# memory-game.net
KiCad netlist of a schematic drawn in EasyEDA
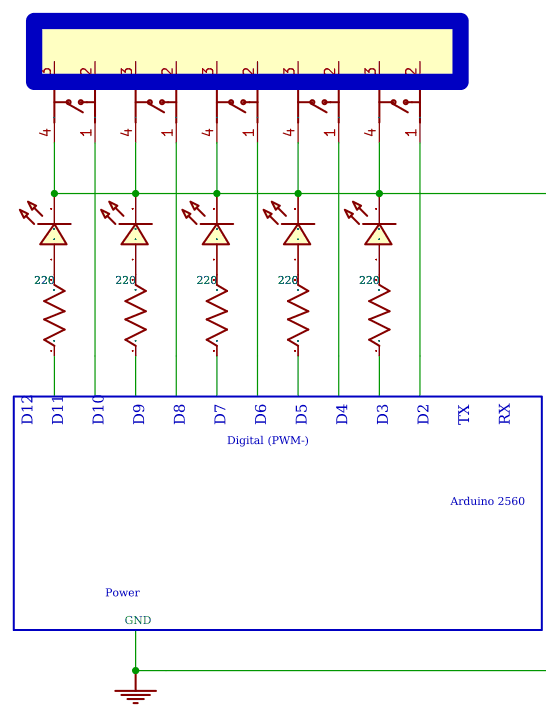
[diagram p0: schematic sheet]

(export (version "E")
  (design (tool "Eeschema 10.0.6"))
  (components
    (comp (ref "KEY1")
      (value "button6*6*8")
      (fields (field (name "BOM_Supplier Part") "C59982"))
      (libsource (lib "") (part "button6*6*8"))
    )
    (comp (ref "KEY2")
      (value "button6*6*8")
      (fields (field (name "BOM_Supplier Part") "C59982"))
      (libsource (lib "") (part "button6*6*8"))
    )
    (comp (ref "KEY3")
      (value "button6*6*8")
      (fields (field (name "BOM_Supplier Part") "C59982"))
      (libsource (lib "") (part "button6*6*8"))
    )
    (comp (ref "KEY4")
      (value "button6*6*8")
      (fields (field (name "BOM_Supplier Part") "C59982"))
      (libsource (lib "") (part "button6*6*8"))
    )
    (comp (ref "KEY5")
      (value "button6*6*8")
      (fields (field (name "BOM_Supplier Part") "C59982"))
      (libsource (lib "") (part "button6*6*8"))
    )
    (comp (ref "LED1")
      (value "LED-0603_R")
      (fields
        (field (name "BOM_Manufacturer Part") "19-217/R6C-AL1M2VY/3T")
        (field (name "BOM_Supplier Part") "C72044")
      )
      (libsource (lib "") (part "LED-0603_R"))
    )
    (comp (ref "LED2")
      (value "LED-0603_R")
      (fields
        (field (name "BOM_Manufacturer Part") "19-217/R6C-AL1M2VY/3T")
        (field (name "BOM_Supplier Part") "C72044")
      )
      (libsource (lib "") (part "LED-0603_R"))
    )
    (comp (ref "LED3")
      (value "LED-0603_R")
      (fields
        (field (name "BOM_Manufacturer Part") "19-217/R6C-AL1M2VY/3T")
        (field (name "BOM_Supplier Part") "C72044")
      )
      (libsource (lib "") (part "LED-0603_R"))
    )
    (comp (ref "LED4")
      (value "LED-0603_R")
      (fields
        (field (name "BOM_Manufacturer Part") "19-217/R6C-AL1M2VY/3T")
        (field (name "BOM_Supplier Part") "C72044")
      )
      (libsource (lib "") (part "LED-0603_R"))
    )
    (comp (ref "LED5")
      (value "LED-0603_R")
      (fields
        (field (name "BOM_Manufacturer Part") "19-217/R6C-AL1M2VY/3T")
        (field (name "BOM_Supplier Part") "C72044")
      )
      (libsource (lib "") (part "LED-0603_R"))
    )
    (comp (ref "R1") (value "220") (libsource (lib "") (part "R_0603_US")))
    (comp (ref "R2") (value "220") (libsource (lib "") (part "R_0603_US")))
    (comp (ref "R3") (value "220") (libsource (lib "") (part "R_0603_US")))
    (comp (ref "R4") (value "220") (libsource (lib "") (part "R_0603_US")))
    (comp (ref "R5") (value "220") (libsource (lib "") (part "R_0603_US")))
  )
  (nets
    (net (code "1") (name "GND") (class "Default")
      (node (ref "KEY1") (pin "4") (pinfunction "4_4") (pintype "unspecified"))
      (node (ref "KEY2") (pin "4") (pinfunction "4_4") (pintype "unspecified"))
      (node (ref "KEY3") (pin "4") (pinfunction "4_4") (pintype "unspecified"))
      (node (ref "KEY4") (pin "4") (pinfunction "4_4") (pintype "unspecified"))
      (node (ref "KEY5") (pin "4") (pinfunction "4_4") (pintype "unspecified"))
      (node (ref "LED1") (pin "2") (pinfunction "2_2") (pintype "unspecified"))
      (node (ref "LED2") (pin "2") (pinfunction "2_2") (pintype "unspecified"))
      (node (ref "LED3") (pin "2") (pinfunction "2_2") (pintype "unspecified"))
      (node (ref "LED4") (pin "2") (pinfunction "2_2") (pintype "unspecified"))
      (node (ref "LED5") (pin "2") (pinfunction "2_2") (pintype "unspecified"))
    )
    (net (code "2") (name "Net-(LED1-Pad1)") (class "Default")
      (node (ref "LED1") (pin "1") (pinfunction "1_1") (pintype "unspecified"))
      (node (ref "R1") (pin "2") (pinfunction "2_2") (pintype "unspecified"))
    )
    (net (code "3") (name "Net-(LED2-Pad1)") (class "Default")
      (node (ref "LED2") (pin "1") (pinfunction "1_1") (pintype "unspecified"))
      (node (ref "R5") (pin "2") (pinfunction "2_2") (pintype "unspecified"))
    )
    (net (code "4") (name "Net-(LED3-Pad1)") (class "Default")
      (node (ref "LED3") (pin "1") (pinfunction "1_1") (pintype "unspecified"))
      (node (ref "R4") (pin "2") (pinfunction "2_2") (pintype "unspecified"))
    )
    (net (code "5") (name "Net-(LED4-Pad1)") (class "Default")
      (node (ref "LED4") (pin "1") (pinfunction "1_1") (pintype "unspecified"))
      (node (ref "R3") (pin "2") (pinfunction "2_2") (pintype "unspecified"))
    )
    (net (code "6") (name "Net-(LED5-Pad1)") (class "Default")
      (node (ref "LED5") (pin "1") (pinfunction "1_1") (pintype "unspecified"))
      (node (ref "R2") (pin "2") (pinfunction "2_2") (pintype "unspecified"))
    )
    (net (code "7") (name "unconnected-(KEY1-Pad1)") (class "Default")
      (node (ref "KEY1") (pin "1") (pinfunction "1_1") (pintype "unspecified"))
    )
    (net (code "8") (name "unconnected-(KEY1-Pad2)") (class "Default")
      (node (ref "KEY1") (pin "2") (pinfunction "2_2") (pintype "unspecified"))
    )
    (net (code "9") (name "unconnected-(KEY1-Pad3)") (class "Default")
      (node (ref "KEY1") (pin "3") (pinfunction "3_3") (pintype "unspecified"))
    )
    (net (code "10") (name "unconnected-(KEY2-Pad1)") (class "Default")
      (node (ref "KEY2") (pin "1") (pinfunction "1_1") (pintype "unspecified"))
    )
    (net (code "11") (name "unconnected-(KEY2-Pad2)") (class "Default")
      (node (ref "KEY2") (pin "2") (pinfunction "2_2") (pintype "unspecified"))
    )
    (net (code "12") (name "unconnected-(KEY2-Pad3)") (class "Default")
      (node (ref "KEY2") (pin "3") (pinfunction "3_3") (pintype "unspecified"))
    )
    (net (code "13") (name "unconnected-(KEY3-Pad1)") (class "Default")
      (node (ref "KEY3") (pin "1") (pinfunction "1_1") (pintype "unspecified"))
    )
    (net (code "14") (name "unconnected-(KEY3-Pad2)") (class "Default")
      (node (ref "KEY3") (pin "2") (pinfunction "2_2") (pintype "unspecified"))
    )
    (net (code "15") (name "unconnected-(KEY3-Pad3)") (class "Default")
      (node (ref "KEY3") (pin "3") (pinfunction "3_3") (pintype "unspecified"))
    )
    (net (code "16") (name "unconnected-(KEY4-Pad1)") (class "Default")
      (node (ref "KEY4") (pin "1") (pinfunction "1_1") (pintype "unspecified"))
    )
    (net (code "17") (name "unconnected-(KEY4-Pad2)") (class "Default")
      (node (ref "KEY4") (pin "2") (pinfunction "2_2") (pintype "unspecified"))
    )
    (net (code "18") (name "unconnected-(KEY4-Pad3)") (class "Default")
      (node (ref "KEY4") (pin "3") (pinfunction "3_3") (pintype "unspecified"))
    )
    (net (code "19") (name "unconnected-(KEY5-Pad1)") (class "Default")
      (node (ref "KEY5") (pin "1") (pinfunction "1_1") (pintype "unspecified"))
    )
    (net (code "20") (name "unconnected-(KEY5-Pad2)") (class "Default")
      (node (ref "KEY5") (pin "2") (pinfunction "2_2") (pintype "unspecified"))
    )
    (net (code "21") (name "unconnected-(KEY5-Pad3)") (class "Default")
      (node (ref "KEY5") (pin "3") (pinfunction "3_3") (pintype "unspecified"))
    )
    (net (code "22") (name "unconnected-(R1-Pad1)") (class "Default")
      (node (ref "R1") (pin "1") (pinfunction "1_1") (pintype "unspecified"))
    )
    (net (code "23") (name "unconnected-(R2-Pad1)") (class "Default")
      (node (ref "R2") (pin "1") (pinfunction "1_1") (pintype "unspecified"))
    )
    (net (code "24") (name "unconnected-(R3-Pad1)") (class "Default")
      (node (ref "R3") (pin "1") (pinfunction "1_1") (pintype "unspecified"))
    )
    (net (code "25") (name "unconnected-(R4-Pad1)") (class "Default")
      (node (ref "R4") (pin "1") (pinfunction "1_1") (pintype "unspecified"))
    )
    (net (code "26") (name "unconnected-(R5-Pad1)") (class "Default")
      (node (ref "R5") (pin "1") (pinfunction "1_1") (pintype "unspecified"))
    )
  )
)
